# audio_amplifier.net
KiCad netlist of a schematic drawn in Altium Designer
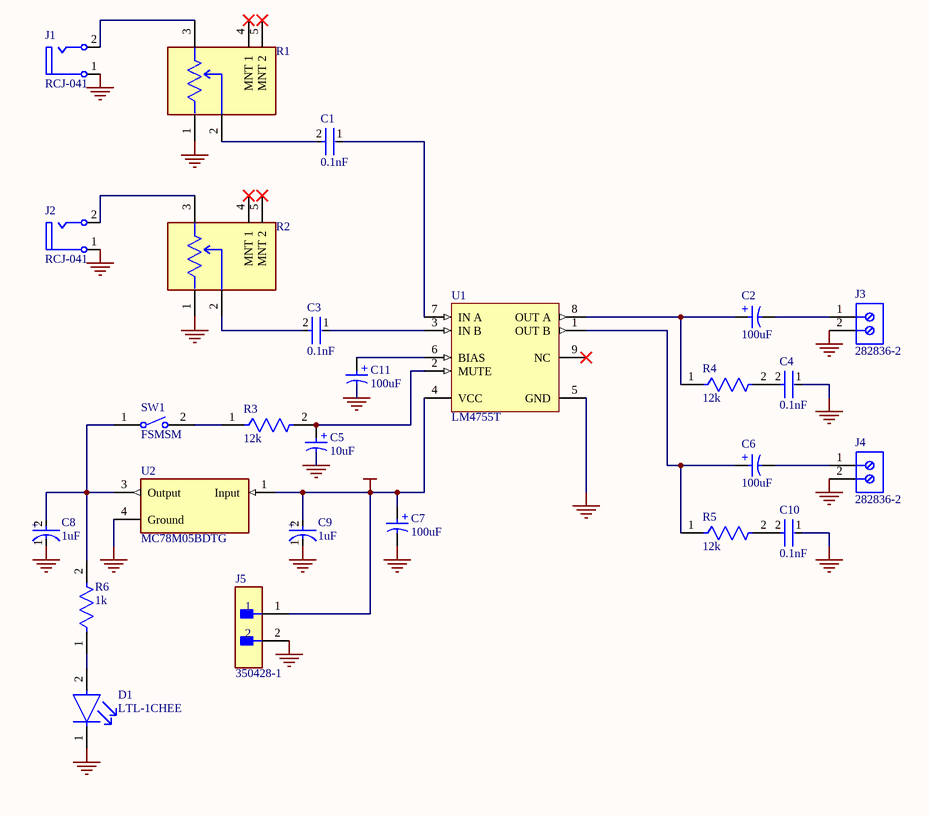
[diagram p0: audio amplifier.SchDoc]

(export (version "E")
  (design (tool "Eeschema 10.0.6"))
  (components
    (comp (ref "C1")
      (value "0.1nF")
      (footprint "FP-562R5GAS10-MFG")
      (description "CAP CER 10000PF 1KV Z5U RADIAL")
      (fields (field (name "TOLERANCE") "20%") (field (name "VOLTAGE") "1kV"))
      (libsource (lib "Altium Content Vault") (part "6d4d395cd7362dd47ce0157d173177e"))
    )
    (comp (ref "C2")
      (value "100uF")
      (footprint "WCAP-ATLL_D8H11.5")
      (description "860160574013 WCAP-ATLL Aluminum Electrolytic Capacitors")
      (fields (field (name "TOLERANCE") "20%"))
      (libsource (lib "Altium Content Vault") (part "Capacitor_Polarized"))
    )
    (comp (ref "C3")
      (value "0.1nF")
      (footprint "FP-562R5GAS10-MFG")
      (description "CAP CER 10000PF 1KV Z5U RADIAL")
      (fields (field (name "TOLERANCE") "20%") (field (name "VOLTAGE") "1kV"))
      (libsource (lib "Altium Content Vault") (part "6d4d395cd7362dd47ce0157d173177e"))
    )
    (comp (ref "C4")
      (value "0.1nF")
      (footprint "FP-562R5GAS10-MFG")
      (description "CAP CER 10000PF 1KV Z5U RADIAL")
      (fields (field (name "TOLERANCE") "20%") (field (name "VOLTAGE") "1kV"))
      (libsource (lib "Altium Content Vault") (part "6d4d395cd7362dd47ce0157d173177e"))
    )
    (comp (ref "C5")
      (value "10uF")
      (footprint "WCAP-ATLL_D8H11.5")
      (description "860160574013 WCAP-ATLL Aluminum Electrolytic Capacitors")
      (fields (field (name "TOLERANCE") "20%"))
      (libsource (lib "Altium Content Vault") (part "Capacitor_Polarized"))
    )
    (comp (ref "C6")
      (value "100uF")
      (footprint "WCAP-ATLL_D8H11.5")
      (description "860160574013 WCAP-ATLL Aluminum Electrolytic Capacitors")
      (fields (field (name "TOLERANCE") "20%"))
      (libsource (lib "Altium Content Vault") (part "Capacitor_Polarized"))
    )
    (comp (ref "C7")
      (value "100uF")
      (footprint "WCAP-ATLL_D8H11.5")
      (description "860160574013 WCAP-ATLL Aluminum Electrolytic Capacitors")
      (fields (field (name "TOLERANCE") "20%"))
      (libsource (lib "Altium Content Vault") (part "Capacitor_Polarized"))
    )
    (comp (ref "C8")
      (value "1uF")
      (footprint "FP-RAD-TH-D_16_0_5-L_25_2-MFG")
      (description "Aluminum Electrolytic Capacitors (Radial Lead Type) 47uF ±20% 400V")
      (fields (field (name "VOLTAGE") "400V") (field (name "TOLERANCE") "20%"))
      (libsource (lib "Altium Content Vault") (part "203bc49f2ac43e59fd269a8c329ed05"))
    )
    (comp (ref "C9")
      (value "1uF")
      (footprint "FP-RAD-TH-D_16_0_5-L_25_2-MFG")
      (description "Aluminum Electrolytic Capacitors (Radial Lead Type) 47uF ±20% 400V")
      (fields (field (name "VOLTAGE") "400V") (field (name "TOLERANCE") "20%"))
      (libsource (lib "Altium Content Vault") (part "203bc49f2ac43e59fd269a8c329ed05"))
    )
    (comp (ref "C10")
      (value "0.1nF")
      (footprint "FP-562R5GAS10-MFG")
      (description "CAP CER 10000PF 1KV Z5U RADIAL")
      (fields (field (name "TOLERANCE") "20%") (field (name "VOLTAGE") "1kV"))
      (libsource (lib "Altium Content Vault") (part "6d4d395cd7362dd47ce0157d173177e"))
    )
    (comp (ref "C11")
      (value "100uF")
      (footprint "WCAP-ATLL_D8H11.5")
      (description "860160574013 WCAP-ATLL Aluminum Electrolytic Capacitors")
      (fields (field (name "TOLERANCE") "20%"))
      (libsource (lib "Altium Content Vault") (part "Capacitor_Polarized"))
    )
    (comp (ref "D1")
      (value "LTL-1CHEE")
      (footprint "FP-LTL-1CHEE-MFG")
      (description "LED RED CLEAR T/H")
      (libsource (lib "Altium Content Vault") (part "8706943c75ba83719d021d2fdc84c58"))
    )
    (comp (ref "J1")
      (value "RCJ-041")
      (footprint "CUI-RCJ-041_V")
      (description "Female RCJ Jack, 2 Position, Height 11.724 mm, Tail Length 4 mm, RoHS, Bulk")
      (libsource (lib "Altium Content Vault") (part "JACK-2CD2"))
    )
    (comp (ref "J2")
      (value "RCJ-041")
      (footprint "CUI-RCJ-041_V")
      (description "Female RCJ Jack, 2 Position, Height 11.724 mm, Tail Length 4 mm, RoHS, Bulk")
      (libsource (lib "Altium Content Vault") (part "JACK-2CD2"))
    )
    (comp (ref "J3")
      (value "282836-2")
      (footprint "TECO-282836-2_V")
      (description "Female Header, Pitch 5 mm, 1 x 2 Position, Height 10 mm, Tail Length 3.5 mm, Rohs, Bulk")
      (fields (field (name "VOLTAGE") "300V") (field (name "MANUFACTURER") "TE Connectivity"))
      (libsource (lib "Altium Content Vault") (part "CN-1P-F-TB2"))
    )
    (comp (ref "J4")
      (value "282836-2")
      (footprint "TECO-282836-2_V")
      (description "Female Header, Pitch 5 mm, 1 x 2 Position, Height 10 mm, Tail Length 3.5 mm, Rohs, Bulk")
      (fields (field (name "VOLTAGE") "300V") (field (name "MANUFACTURER") "TE Connectivity"))
      (libsource (lib "Altium Content Vault") (part "CN-1P-F-TB2"))
    )
    (comp (ref "J5")
      (value "350428-1")
      (footprint "FP-350428-1-MFG")
      (description "CONN HEADER VERT 2POS 6.35MM")
      (fields
        (field (name "OCTOPART") "https://octopart.com/350428-1-te+connectivity-46505355")
        (field (name "MANUFACTURER") "TE Connectivity")
      )
      (libsource (lib "Altium Content Vault") (part "3bc925449376181038e59eaffc5286c"))
    )
    (comp (ref "R1")
      (value "PTV09A-4225F-B103")
      (footprint "FP-PTV09A-4-MFG")
      (description "POT 10K OHM 1/20W CARBON LINEAR")
      (fields (field (name "TOLERANCE") "20%"))
      (libsource (lib "Altium Content Vault") (part "705d11b747745a787204d796a5f3d12"))
    )
    (comp (ref "R2")
      (value "PTV09A-4225F-B103")
      (footprint "FP-PTV09A-4-MFG")
      (description "POT 10K OHM 1/20W CARBON LINEAR")
      (fields (field (name "TOLERANCE") "20%"))
      (libsource (lib "Altium Content Vault") (part "705d11b747745a787204d796a5f3d12"))
    )
    (comp (ref "R3")
      (value "12k")
      (footprint "FP-CF14-MFG")
      (description "RES 7.5K OHM 1/4W 5% AXIAL")
      (fields (field (name "TOLERANCE") "5%"))
      (libsource (lib "Altium Content Vault") (part "1029c3af85768c4190bb7ad29bc67b5"))
    )
    (comp (ref "R4")
      (value "12k")
      (footprint "FP-CF14-MFG")
      (description "RES 7.5K OHM 1/4W 5% AXIAL")
      (fields (field (name "TOLERANCE") "5%"))
      (libsource (lib "Altium Content Vault") (part "1029c3af85768c4190bb7ad29bc67b5"))
    )
    (comp (ref "R5")
      (value "12k")
      (footprint "FP-CF14-MFG")
      (description "RES 7.5K OHM 1/4W 5% AXIAL")
      (fields (field (name "TOLERANCE") "5%"))
      (libsource (lib "Altium Content Vault") (part "1029c3af85768c4190bb7ad29bc67b5"))
    )
    (comp (ref "R6")
      (value "1k")
      (footprint "FP-CF14-MFG")
      (description "RES 7.5K OHM 1/4W 5% AXIAL")
      (fields (field (name "TOLERANCE") "5%"))
      (libsource (lib "Altium Content Vault") (part "1029c3af85768c4190bb7ad29bc67b5"))
    )
    (comp (ref "SW1")
      (value "FSMSM")
      (footprint "TECO-FSMSM-2_V")
      (description "FSMSM Push Button Switch, 50 mA, -35 to 85 degC, 2-Pin SMD, RoHS, Bulk")
      (fields (field (name "MANUFACTURER") "TE Connectivity"))
      (libsource (lib "Altium Content Vault") (part "SW-SPST-2_C"))
    )
    (comp (ref "U1")
      (value "LM4755T")
      (footprint "TA09A")
      (description "Stereo 11W Audio Power Amplifier with Mute, 9-pin TO-220")
      (fields (field (name "MANUFACTURER") "National Semiconductor"))
      (libsource (lib "Altium Content Vault") (part "AMP-APA-LM4755-9"))
    )
    (comp (ref "U2")
      (value "MC78M05BDTG")
      (footprint "FP-369C-MFG")
      (description "IC REG LINEAR 5V 500MA DPAK")
      (fields
        (field (name "OCTOPART") "https://octopart.com/mc78m05bdtg-on+semiconductor-1009693")
        (field (name "MANUFACTURER") "ON Semiconductor")
      )
      (libsource (lib "Altium Content Vault") (part "fada0808d73a4553a4ce570dcefa151"))
    )
  )
  (nets
    (net (code "1") (name "GND") (class "Default")
      (node (ref "C10") (pin "1") (pinfunction "1_1") (pintype "passive"))
      (node (ref "C11") (pin "2") (pinfunction "N_2") (pintype "passive"))
      (node (ref "C4") (pin "1") (pinfunction "1_1") (pintype "passive"))
      (node (ref "C5") (pin "2") (pinfunction "N_2") (pintype "passive"))
      (node (ref "C7") (pin "2") (pinfunction "N_2") (pintype "passive"))
      (node (ref "C8") (pin "1") (pinfunction "C_1") (pintype "passive"))
      (node (ref "C9") (pin "1") (pinfunction "C_1") (pintype "passive"))
      (node (ref "D1") (pin "1") (pinfunction "C_1") (pintype "passive"))
      (node (ref "J1") (pin "1") (pinfunction "1_1") (pintype "passive"))
      (node (ref "J2") (pin "1") (pinfunction "1_1") (pintype "passive"))
      (node (ref "J3") (pin "2") (pinfunction "2_2") (pintype "passive"))
      (node (ref "J4") (pin "2") (pinfunction "2_2") (pintype "passive"))
      (node (ref "J5") (pin "2") (pinfunction "2_2") (pintype "passive"))
      (node (ref "R1") (pin "1") (pinfunction "1_1") (pintype "passive"))
      (node (ref "R2") (pin "1") (pinfunction "1_1") (pintype "passive"))
      (node (ref "U1") (pin "5") (pinfunction "GND_5") (pintype "power_in"))
      (node (ref "U2") (pin "4") (pinfunction "Ground_4") (pintype "power_in"))
    )
    (net (code "2") (name "Net-(C1-Pad2)") (class "Default")
      (node (ref "C1") (pin "2") (pinfunction "2_2") (pintype "passive"))
      (node (ref "R1") (pin "2") (pinfunction "2_2") (pintype "passive"))
    )
    (net (code "3") (name "Net-(C2-N)") (class "Default")
      (node (ref "C2") (pin "2") (pinfunction "N_2") (pintype "passive"))
      (node (ref "J3") (pin "1") (pinfunction "1_1") (pintype "passive"))
    )
    (net (code "4") (name "Net-(C2-P)") (class "Default")
      (node (ref "C2") (pin "1") (pinfunction "P_1") (pintype "passive"))
      (node (ref "R4") (pin "1") (pinfunction "1_1") (pintype "passive"))
      (node (ref "U1") (pin "8") (pinfunction "OUT_A_8") (pintype "output"))
    )
    (net (code "5") (name "Net-(C3-Pad2)") (class "Default")
      (node (ref "C3") (pin "2") (pinfunction "2_2") (pintype "passive"))
      (node (ref "R2") (pin "2") (pinfunction "2_2") (pintype "passive"))
    )
    (net (code "6") (name "Net-(C4-Pad2)") (class "Default")
      (node (ref "C4") (pin "2") (pinfunction "2_2") (pintype "passive"))
      (node (ref "R4") (pin "2") (pinfunction "2_2") (pintype "passive"))
    )
    (net (code "7") (name "Net-(C5-P)") (class "Default")
      (node (ref "C5") (pin "1") (pinfunction "P_1") (pintype "passive"))
      (node (ref "R3") (pin "2") (pinfunction "2_2") (pintype "passive"))
      (node (ref "U1") (pin "2") (pinfunction "MUTE_2") (pintype "input"))
    )
    (net (code "8") (name "Net-(C6-N)") (class "Default")
      (node (ref "C6") (pin "2") (pinfunction "N_2") (pintype "passive"))
      (node (ref "J4") (pin "1") (pinfunction "1_1") (pintype "passive"))
    )
    (net (code "9") (name "Net-(C6-P)") (class "Default")
      (node (ref "C6") (pin "1") (pinfunction "P_1") (pintype "passive"))
      (node (ref "R5") (pin "1") (pinfunction "1_1") (pintype "passive"))
      (node (ref "U1") (pin "1") (pinfunction "OUT_B_1") (pintype "output"))
    )
    (net (code "10") (name "Net-(C8-A)") (class "Default")
      (node (ref "C8") (pin "2") (pinfunction "A_2") (pintype "passive"))
      (node (ref "R6") (pin "2") (pinfunction "2_2") (pintype "passive"))
      (node (ref "SW1") (pin "1") (pinfunction "1_1") (pintype "passive"))
      (node (ref "U2") (pin "3") (pinfunction "Output_3") (pintype "output"))
    )
    (net (code "11") (name "Net-(C10-Pad2)") (class "Default")
      (node (ref "C10") (pin "2") (pinfunction "2_2") (pintype "passive"))
      (node (ref "R5") (pin "2") (pinfunction "2_2") (pintype "passive"))
    )
    (net (code "12") (name "Net-(C11-P)") (class "Default")
      (node (ref "C11") (pin "1") (pinfunction "P_1") (pintype "passive"))
      (node (ref "U1") (pin "6") (pinfunction "BIAS_6") (pintype "input"))
    )
    (net (code "13") (name "Net-(D1-A)") (class "Default")
      (node (ref "D1") (pin "2") (pinfunction "A_2") (pintype "passive"))
      (node (ref "R6") (pin "1") (pinfunction "1_1") (pintype "passive"))
    )
    (net (code "14") (name "Net-(J1-Pad2)") (class "Default")
      (node (ref "J1") (pin "2") (pinfunction "2_2") (pintype "passive"))
      (node (ref "R1") (pin "3") (pinfunction "3_3") (pintype "passive"))
    )
    (net (code "15") (name "Net-(J2-Pad2)") (class "Default")
      (node (ref "J2") (pin "2") (pinfunction "2_2") (pintype "passive"))
      (node (ref "R2") (pin "3") (pinfunction "3_3") (pintype "passive"))
    )
    (net (code "16") (name "Net-(R3-Pad1)") (class "Default")
      (node (ref "R3") (pin "1") (pinfunction "1_1") (pintype "passive"))
      (node (ref "SW1") (pin "2") (pinfunction "2_2") (pintype "passive"))
    )
    (net (code "17") (name "Net-(U1-IN_A)") (class "Default")
      (node (ref "C1") (pin "1") (pinfunction "1_1") (pintype "passive"))
      (node (ref "U1") (pin "7") (pinfunction "IN_A_7") (pintype "input"))
    )
    (net (code "18") (name "Net-(U1-IN_B)") (class "Default")
      (node (ref "C3") (pin "1") (pinfunction "1_1") (pintype "passive"))
      (node (ref "U1") (pin "3") (pinfunction "IN_B_3") (pintype "input"))
    )
    (net (code "19") (name "VCC") (class "Default")
      (node (ref "C7") (pin "1") (pinfunction "P_1") (pintype "passive"))
      (node (ref "C9") (pin "2") (pinfunction "A_2") (pintype "passive"))
      (node (ref "J5") (pin "1") (pinfunction "1_1") (pintype "passive"))
      (node (ref "U1") (pin "4") (pinfunction "VCC_4") (pintype "power_in"))
      (node (ref "U2") (pin "1") (pinfunction "Input_1") (pintype "input"))
    )
    (net (code "20") (name "unconnected-(R1-MNT_1-Pad4)") (class "Default")
      (node (ref "R1") (pin "4") (pinfunction "MNT_1_4") (pintype "passive+no_connect"))
    )
    (net (code "21") (name "unconnected-(R1-MNT_2-Pad5)") (class "Default")
      (node (ref "R1") (pin "5") (pinfunction "MNT_2_5") (pintype "passive+no_connect"))
    )
    (net (code "22") (name "unconnected-(R2-MNT_1-Pad4)") (class "Default")
      (node (ref "R2") (pin "4") (pinfunction "MNT_1_4") (pintype "passive+no_connect"))
    )
    (net (code "23") (name "unconnected-(R2-MNT_2-Pad5)") (class "Default")
      (node (ref "R2") (pin "5") (pinfunction "MNT_2_5") (pintype "passive+no_connect"))
    )
    (net (code "24") (name "unconnected-(U1-NC-Pad9)") (class "Default")
      (node (ref "U1") (pin "9") (pinfunction "NC_9") (pintype "passive+no_connect"))
    )
  )
)
